# SCH_AudioSwitcher_2026-03-13.net
KiCad netlist of a schematic drawn in EasyEDA
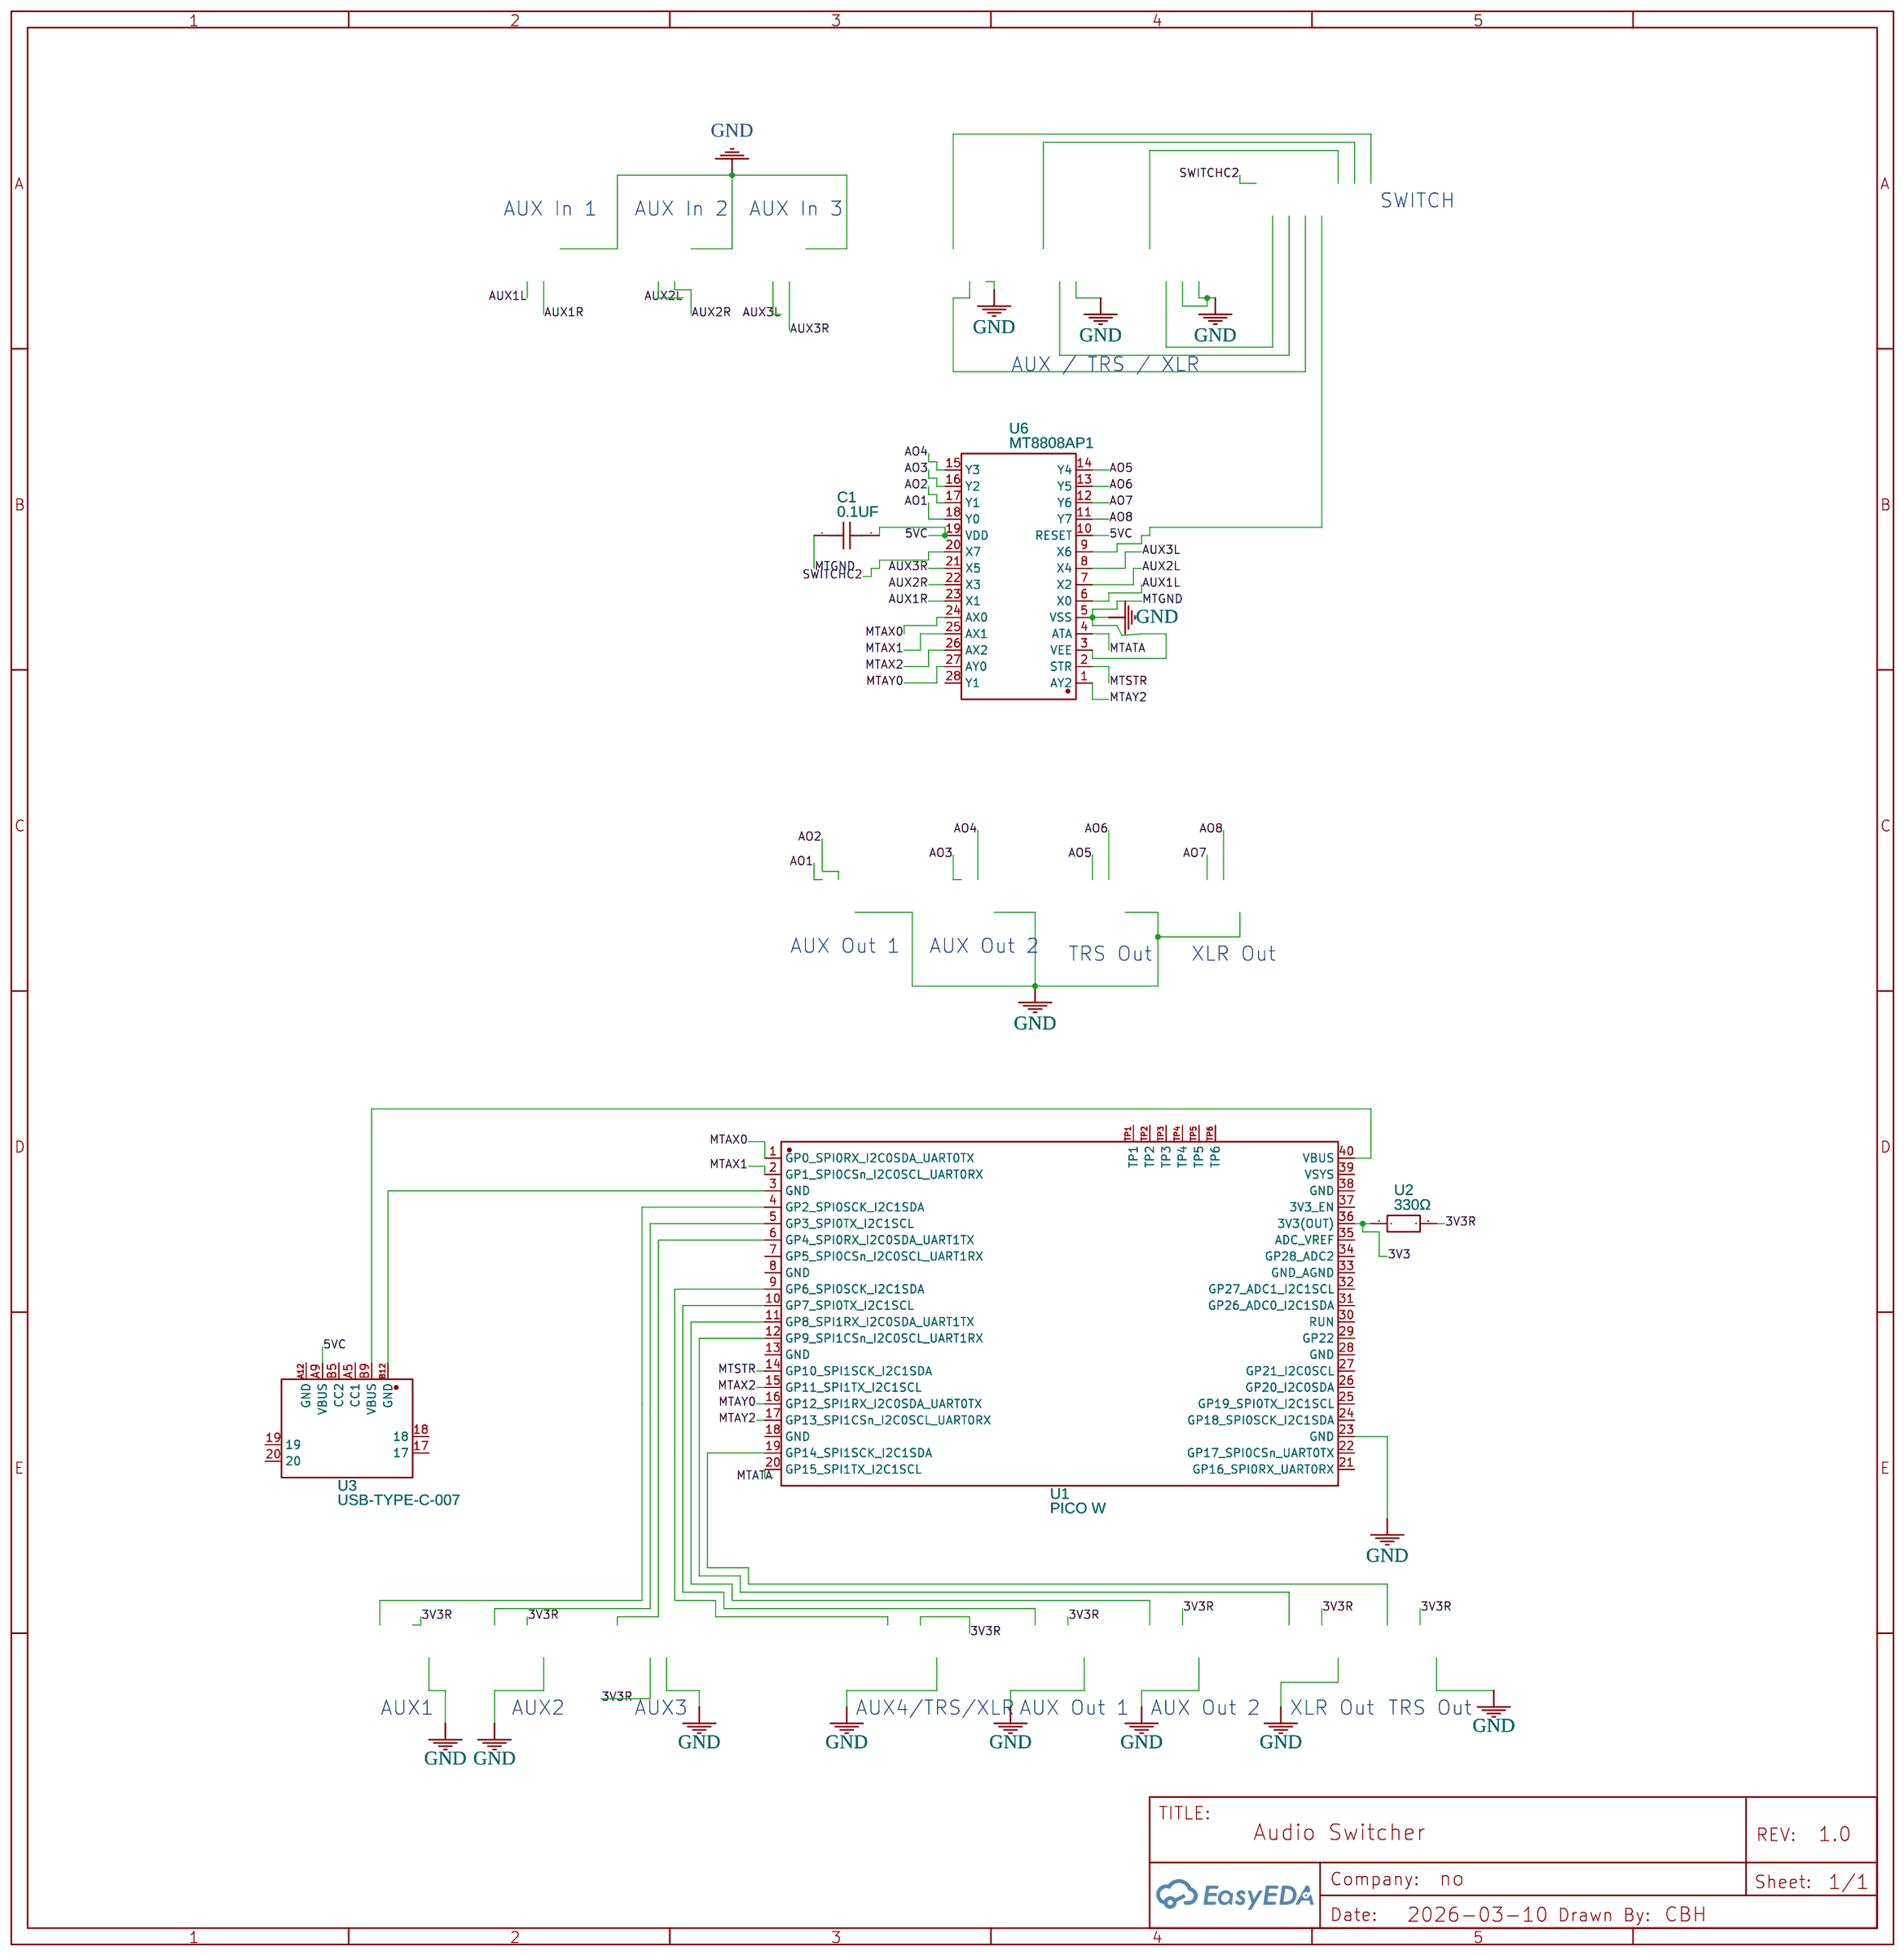
[diagram p0: schematic sheet]

(export (version "E")
  (design (tool "Eeschema 10.0.6"))
  (components
    (comp (ref "C1")
      (value "0.1UF")
      (fields
        (field (name "Manufacturer Part") "250V 0.1UF 5% CBBCapacitor")
        (field (name "Manufacturer") "ReliaPro")
      )
      (libsource (lib "") (part "250V 0.1UF 5% CBBCapacitor"))
    )
    (comp (ref "U1")
      (value "PICO W")
      (fields (field (name "Manufacturer") "Raspberry Pi(树莓派)"))
      (libsource (lib "") (part "PICO W"))
    )
    (comp (ref "U2")
      (value "330Ω")
      (fields (field (name "Manufacturer Part") "SCR0603J330R") (field (name "Manufacturer") "VO(翔胜)"))
      (libsource (lib "") (part "SCR0603J330R"))
    )
    (comp (ref "U3")
      (value "USB-TYPE-C-007")
      (fields (field (name "Manufacturer") "DEALON(德艺隆)"))
      (libsource (lib "") (part "USB-TYPE-C-007"))
    )
    (comp (ref "U6")
      (value "MT8808AP1")
      (fields (field (name "Manufacturer") "MICROCHIP(美国微芯)"))
      (libsource (lib "") (part "MT8808AP1"))
    )
  )
  (nets
    (net (code "1") (name "/3V3") (class "Default")
      (node (ref "U1") (pin "36") (pinfunction "3V3(OUT)_36") (pintype "unspecified"))
      (node (ref "U2") (pin "1") (pinfunction "1_1") (pintype "unspecified"))
    )
    (net (code "2") (name "/3V3R") (class "Default")
      (node (ref "U2") (pin "2") (pinfunction "2_2") (pintype "unspecified"))
    )
    (net (code "3") (name "/5VC") (class "Default")
      (node (ref "C1") (pin "2") (pinfunction "2_2") (pintype "unspecified"))
      (node (ref "U3") (pin "A9") (pinfunction "VBUS_A9") (pintype "unspecified"))
      (node (ref "U6") (pin "10") (pinfunction "RESET_10") (pintype "unspecified"))
      (node (ref "U6") (pin "19") (pinfunction "VDD_19") (pintype "unspecified"))
    )
    (net (code "4") (name "/AO1") (class "Default")
      (node (ref "U6") (pin "18") (pinfunction "Y0_18") (pintype "unspecified"))
    )
    (net (code "5") (name "/AO2") (class "Default")
      (node (ref "U6") (pin "17") (pinfunction "Y1_17") (pintype "unspecified"))
    )
    (net (code "6") (name "/AO3") (class "Default")
      (node (ref "U6") (pin "16") (pinfunction "Y2_16") (pintype "unspecified"))
    )
    (net (code "7") (name "/AO4") (class "Default")
      (node (ref "U6") (pin "15") (pinfunction "Y3_15") (pintype "unspecified"))
    )
    (net (code "8") (name "/AO5") (class "Default")
      (node (ref "U6") (pin "14") (pinfunction "Y4_14") (pintype "unspecified"))
    )
    (net (code "9") (name "/AO6") (class "Default")
      (node (ref "U6") (pin "13") (pinfunction "Y5_13") (pintype "unspecified"))
    )
    (net (code "10") (name "/AO7") (class "Default")
      (node (ref "U6") (pin "12") (pinfunction "Y6_12") (pintype "unspecified"))
    )
    (net (code "11") (name "/AO8") (class "Default")
      (node (ref "U6") (pin "11") (pinfunction "Y7_11") (pintype "unspecified"))
    )
    (net (code "12") (name "/AUX1L") (class "Default")
      (node (ref "U6") (pin "6") (pinfunction "X0_6") (pintype "unspecified"))
    )
    (net (code "13") (name "/AUX1R") (class "Default")
      (node (ref "U6") (pin "23") (pinfunction "X1_23") (pintype "unspecified"))
    )
    (net (code "14") (name "/AUX2L") (class "Default")
      (node (ref "U6") (pin "7") (pinfunction "X2_7") (pintype "unspecified"))
    )
    (net (code "15") (name "/AUX2R") (class "Default")
      (node (ref "U6") (pin "22") (pinfunction "X3_22") (pintype "unspecified"))
    )
    (net (code "16") (name "/AUX3L") (class "Default")
      (node (ref "U6") (pin "8") (pinfunction "X4_8") (pintype "unspecified"))
    )
    (net (code "17") (name "/AUX3R") (class "Default")
      (node (ref "U6") (pin "21") (pinfunction "X5_21") (pintype "unspecified"))
    )
    (net (code "18") (name "/MTATA") (class "Default")
      (node (ref "U1") (pin "20") (pinfunction "GP15_SPI1TX_I2C1SCL_20") (pintype "unspecified"))
      (node (ref "U6") (pin "4") (pinfunction "ATA_4") (pintype "unspecified"))
    )
    (net (code "19") (name "/MTAX0") (class "Default")
      (node (ref "U1") (pin "1") (pinfunction "GP0_SPI0RX_I2C0SDA_UART0TX_1") (pintype "unspecified"))
      (node (ref "U6") (pin "24") (pinfunction "AX0_24") (pintype "unspecified"))
    )
    (net (code "20") (name "/MTAX1") (class "Default")
      (node (ref "U1") (pin "2") (pinfunction "GP1_SPI0CSn_I2C0SCL_UART0RX_2") (pintype "unspecified"))
      (node (ref "U6") (pin "25") (pinfunction "AX1_25") (pintype "unspecified"))
    )
    (net (code "21") (name "/MTAX2") (class "Default")
      (node (ref "U1") (pin "15") (pinfunction "GP11_SPI1TX_I2C1SCL_15") (pintype "unspecified"))
      (node (ref "U6") (pin "26") (pinfunction "AX2_26") (pintype "unspecified"))
    )
    (net (code "22") (name "/MTAY0") (class "Default")
      (node (ref "U1") (pin "16") (pinfunction "GP12_SPI1RX_I2C0SDA_UART0TX_16") (pintype "unspecified"))
      (node (ref "U6") (pin "27") (pinfunction "AY0_27") (pintype "unspecified"))
    )
    (net (code "23") (name "/MTAY2") (class "Default")
      (node (ref "U1") (pin "17") (pinfunction "GP13_SPI1CSn_I2C0SCL_UART0RX_17") (pintype "unspecified"))
      (node (ref "U6") (pin "1") (pinfunction "AY2_1") (pintype "unspecified"))
    )
    (net (code "24") (name "/MTSTR") (class "Default")
      (node (ref "U1") (pin "14") (pinfunction "GP10_SPI1SCK_I2C1SDA_14") (pintype "unspecified"))
      (node (ref "U6") (pin "2") (pinfunction "STR_2") (pintype "unspecified"))
    )
    (net (code "25") (name "/SWITCHC2") (class "Default")
      (node (ref "U6") (pin "20") (pinfunction "X7_20") (pintype "unspecified"))
    )
    (net (code "26") (name "GND") (class "Default")
      (node (ref "C1") (pin "1") (pinfunction "1_1") (pintype "unspecified"))
      (node (ref "U1") (pin "23") (pinfunction "GND_23") (pintype "unspecified"))
      (node (ref "U6") (pin "3") (pinfunction "VEE_3") (pintype "unspecified"))
      (node (ref "U6") (pin "5") (pinfunction "VSS_5") (pintype "unspecified"))
    )
    (net (code "27") (name "Net-(U1-GND-Pad3)") (class "Default")
      (node (ref "U1") (pin "3") (pinfunction "GND_3") (pintype "unspecified"))
      (node (ref "U3") (pin "B12") (pinfunction "GND_B12") (pintype "unspecified"))
    )
    (net (code "28") (name "Net-(U1-VBUS)") (class "Default")
      (node (ref "U1") (pin "40") (pinfunction "VBUS_40") (pintype "unspecified"))
      (node (ref "U3") (pin "B9") (pinfunction "VBUS_B9") (pintype "unspecified"))
    )
    (net (code "29") (name "unconnected-(U1-3V3_EN-Pad37)") (class "Default")
      (node (ref "U1") (pin "37") (pinfunction "3V3_EN_37") (pintype "unspecified"))
    )
    (net (code "30") (name "unconnected-(U1-ADC_VREF-Pad35)") (class "Default")
      (node (ref "U1") (pin "35") (pinfunction "ADC_VREF_35") (pintype "unspecified"))
    )
    (net (code "31") (name "unconnected-(U1-GND-Pad8)") (class "Default")
      (node (ref "U1") (pin "8") (pinfunction "GND_8") (pintype "unspecified"))
    )
    (net (code "32") (name "unconnected-(U1-GND-Pad13)") (class "Default")
      (node (ref "U1") (pin "13") (pinfunction "GND_13") (pintype "unspecified"))
    )
    (net (code "33") (name "unconnected-(U1-GND-Pad18)") (class "Default")
      (node (ref "U1") (pin "18") (pinfunction "GND_18") (pintype "unspecified"))
    )
    (net (code "34") (name "unconnected-(U1-GND-Pad28)") (class "Default")
      (node (ref "U1") (pin "28") (pinfunction "GND_28") (pintype "unspecified"))
    )
    (net (code "35") (name "unconnected-(U1-GND-Pad38)") (class "Default")
      (node (ref "U1") (pin "38") (pinfunction "GND_38") (pintype "unspecified"))
    )
    (net (code "36") (name "unconnected-(U1-GND_AGND-Pad33)") (class "Default")
      (node (ref "U1") (pin "33") (pinfunction "GND_AGND_33") (pintype "unspecified"))
    )
    (net (code "37") (name "unconnected-(U1-GP2_SPI0SCK_I2C1SDA-Pad4)") (class "Default")
      (node (ref "U1") (pin "4") (pinfunction "GP2_SPI0SCK_I2C1SDA_4") (pintype "unspecified"))
    )
    (net (code "38") (name "unconnected-(U1-GP3_SPI0TX_I2C1SCL-Pad5)") (class "Default")
      (node (ref "U1") (pin "5") (pinfunction "GP3_SPI0TX_I2C1SCL_5") (pintype "unspecified"))
    )
    (net (code "39") (name "unconnected-(U1-GP4_SPI0RX_I2C0SDA_UART1TX-Pad6)") (class "Default")
      (node (ref "U1") (pin "6") (pinfunction "GP4_SPI0RX_I2C0SDA_UART1TX_6") (pintype "unspecified"))
    )
    (net (code "40") (name "unconnected-(U1-GP5_SPI0CSn_I2C0SCL_UART1RX-Pad7)") (class "Default")
      (node (ref "U1") (pin "7") (pinfunction "GP5_SPI0CSn_I2C0SCL_UART1RX_7") (pintype "unspecified"))
    )
    (net (code "41") (name "unconnected-(U1-GP6_SPI0SCK_I2C1SDA-Pad9)") (class "Default")
      (node (ref "U1") (pin "9") (pinfunction "GP6_SPI0SCK_I2C1SDA_9") (pintype "unspecified"))
    )
    (net (code "42") (name "unconnected-(U1-GP7_SPI0TX_I2C1SCL-Pad10)") (class "Default")
      (node (ref "U1") (pin "10") (pinfunction "GP7_SPI0TX_I2C1SCL_10") (pintype "unspecified"))
    )
    (net (code "43") (name "unconnected-(U1-GP8_SPI1RX_I2C0SDA_UART1TX-Pad11)") (class "Default")
      (node (ref "U1") (pin "11") (pinfunction "GP8_SPI1RX_I2C0SDA_UART1TX_11") (pintype "unspecified"))
    )
    (net (code "44") (name "unconnected-(U1-GP9_SPI1CSn_I2C0SCL_UART1RX-Pad12)") (class "Default")
      (node (ref "U1") (pin "12") (pinfunction "GP9_SPI1CSn_I2C0SCL_UART1RX_12") (pintype "unspecified"))
    )
    (net (code "45") (name "unconnected-(U1-GP14_SPI1SCK_I2C1SDA-Pad19)") (class "Default")
      (node (ref "U1") (pin "19") (pinfunction "GP14_SPI1SCK_I2C1SDA_19") (pintype "unspecified"))
    )
    (net (code "46") (name "unconnected-(U1-GP16_SPI0RX_UART0RX-Pad21)") (class "Default")
      (node (ref "U1") (pin "21") (pinfunction "GP16_SPI0RX_UART0RX_21") (pintype "unspecified"))
    )
    (net (code "47") (name "unconnected-(U1-GP17_SPI0CSn_UART0TX-Pad22)") (class "Default")
      (node (ref "U1") (pin "22") (pinfunction "GP17_SPI0CSn_UART0TX_22") (pintype "unspecified"))
    )
    (net (code "48") (name "unconnected-(U1-GP18_SPI0SCK_I2C1SDA-Pad24)") (class "Default")
      (node (ref "U1") (pin "24") (pinfunction "GP18_SPI0SCK_I2C1SDA_24") (pintype "unspecified"))
    )
    (net (code "49") (name "unconnected-(U1-GP19_SPI0TX_I2C1SCL-Pad25)") (class "Default")
      (node (ref "U1") (pin "25") (pinfunction "GP19_SPI0TX_I2C1SCL_25") (pintype "unspecified"))
    )
    (net (code "50") (name "unconnected-(U1-GP20_I2C0SDA-Pad26)") (class "Default")
      (node (ref "U1") (pin "26") (pinfunction "GP20_I2C0SDA_26") (pintype "unspecified"))
    )
    (net (code "51") (name "unconnected-(U1-GP21_I2C0SCL-Pad27)") (class "Default")
      (node (ref "U1") (pin "27") (pinfunction "GP21_I2C0SCL_27") (pintype "unspecified"))
    )
    (net (code "52") (name "unconnected-(U1-GP22-Pad29)") (class "Default")
      (node (ref "U1") (pin "29") (pinfunction "GP22_29") (pintype "unspecified"))
    )
    (net (code "53") (name "unconnected-(U1-GP26_ADC0_I2C1SDA-Pad31)") (class "Default")
      (node (ref "U1") (pin "31") (pinfunction "GP26_ADC0_I2C1SDA_31") (pintype "unspecified"))
    )
    (net (code "54") (name "unconnected-(U1-GP27_ADC1_I2C1SCL-Pad32)") (class "Default")
      (node (ref "U1") (pin "32") (pinfunction "GP27_ADC1_I2C1SCL_32") (pintype "unspecified"))
    )
    (net (code "55") (name "unconnected-(U1-GP28_ADC2-Pad34)") (class "Default")
      (node (ref "U1") (pin "34") (pinfunction "GP28_ADC2_34") (pintype "unspecified"))
    )
    (net (code "56") (name "unconnected-(U1-PadTP1)") (class "Default")
      (node (ref "U1") (pin "TP1") (pinfunction "TP1_TP1") (pintype "unspecified"))
    )
    (net (code "57") (name "unconnected-(U1-PadTP2)") (class "Default")
      (node (ref "U1") (pin "TP2") (pinfunction "TP2_TP2") (pintype "unspecified"))
    )
    (net (code "58") (name "unconnected-(U1-PadTP3)") (class "Default")
      (node (ref "U1") (pin "TP3") (pinfunction "TP3_TP3") (pintype "unspecified"))
    )
    (net (code "59") (name "unconnected-(U1-PadTP4)") (class "Default")
      (node (ref "U1") (pin "TP4") (pinfunction "TP4_TP4") (pintype "unspecified"))
    )
    (net (code "60") (name "unconnected-(U1-PadTP5)") (class "Default")
      (node (ref "U1") (pin "TP5") (pinfunction "TP5_TP5") (pintype "unspecified"))
    )
    (net (code "61") (name "unconnected-(U1-PadTP6)") (class "Default")
      (node (ref "U1") (pin "TP6") (pinfunction "TP6_TP6") (pintype "unspecified"))
    )
    (net (code "62") (name "unconnected-(U1-RUN-Pad30)") (class "Default")
      (node (ref "U1") (pin "30") (pinfunction "RUN_30") (pintype "unspecified"))
    )
    (net (code "63") (name "unconnected-(U1-VSYS-Pad39)") (class "Default")
      (node (ref "U1") (pin "39") (pinfunction "VSYS_39") (pintype "unspecified"))
    )
    (net (code "64") (name "unconnected-(U3-CC1-PadA5)") (class "Default")
      (node (ref "U3") (pin "A5") (pinfunction "CC1_A5") (pintype "unspecified"))
    )
    (net (code "65") (name "unconnected-(U3-CC2-PadB5)") (class "Default")
      (node (ref "U3") (pin "B5") (pinfunction "CC2_B5") (pintype "unspecified"))
    )
    (net (code "66") (name "unconnected-(U3-GND-PadA12)") (class "Default")
      (node (ref "U3") (pin "A12") (pinfunction "GND_A12") (pintype "unspecified"))
    )
    (net (code "67") (name "unconnected-(U3-Pad17)") (class "Default")
      (node (ref "U3") (pin "17") (pinfunction "17_17") (pintype "unspecified"))
    )
    (net (code "68") (name "unconnected-(U3-Pad18)") (class "Default")
      (node (ref "U3") (pin "18") (pinfunction "18_18") (pintype "unspecified"))
    )
    (net (code "69") (name "unconnected-(U3-Pad19)") (class "Default")
      (node (ref "U3") (pin "19") (pinfunction "19_19") (pintype "unspecified"))
    )
    (net (code "70") (name "unconnected-(U3-Pad20)") (class "Default")
      (node (ref "U3") (pin "20") (pinfunction "20_20") (pintype "unspecified"))
    )
    (net (code "71") (name "unconnected-(U6-X6-Pad9)") (class "Default")
      (node (ref "U6") (pin "9") (pinfunction "X6_9") (pintype "unspecified"))
    )
    (net (code "72") (name "unconnected-(U6-Y1-Pad28)") (class "Default")
      (node (ref "U6") (pin "28") (pinfunction "Y1_28") (pintype "unspecified"))
    )
  )
)
